# ATSAM4E16EA_AU_Main_Controller.net
KiCad netlist of a schematic drawn in Altium Designer
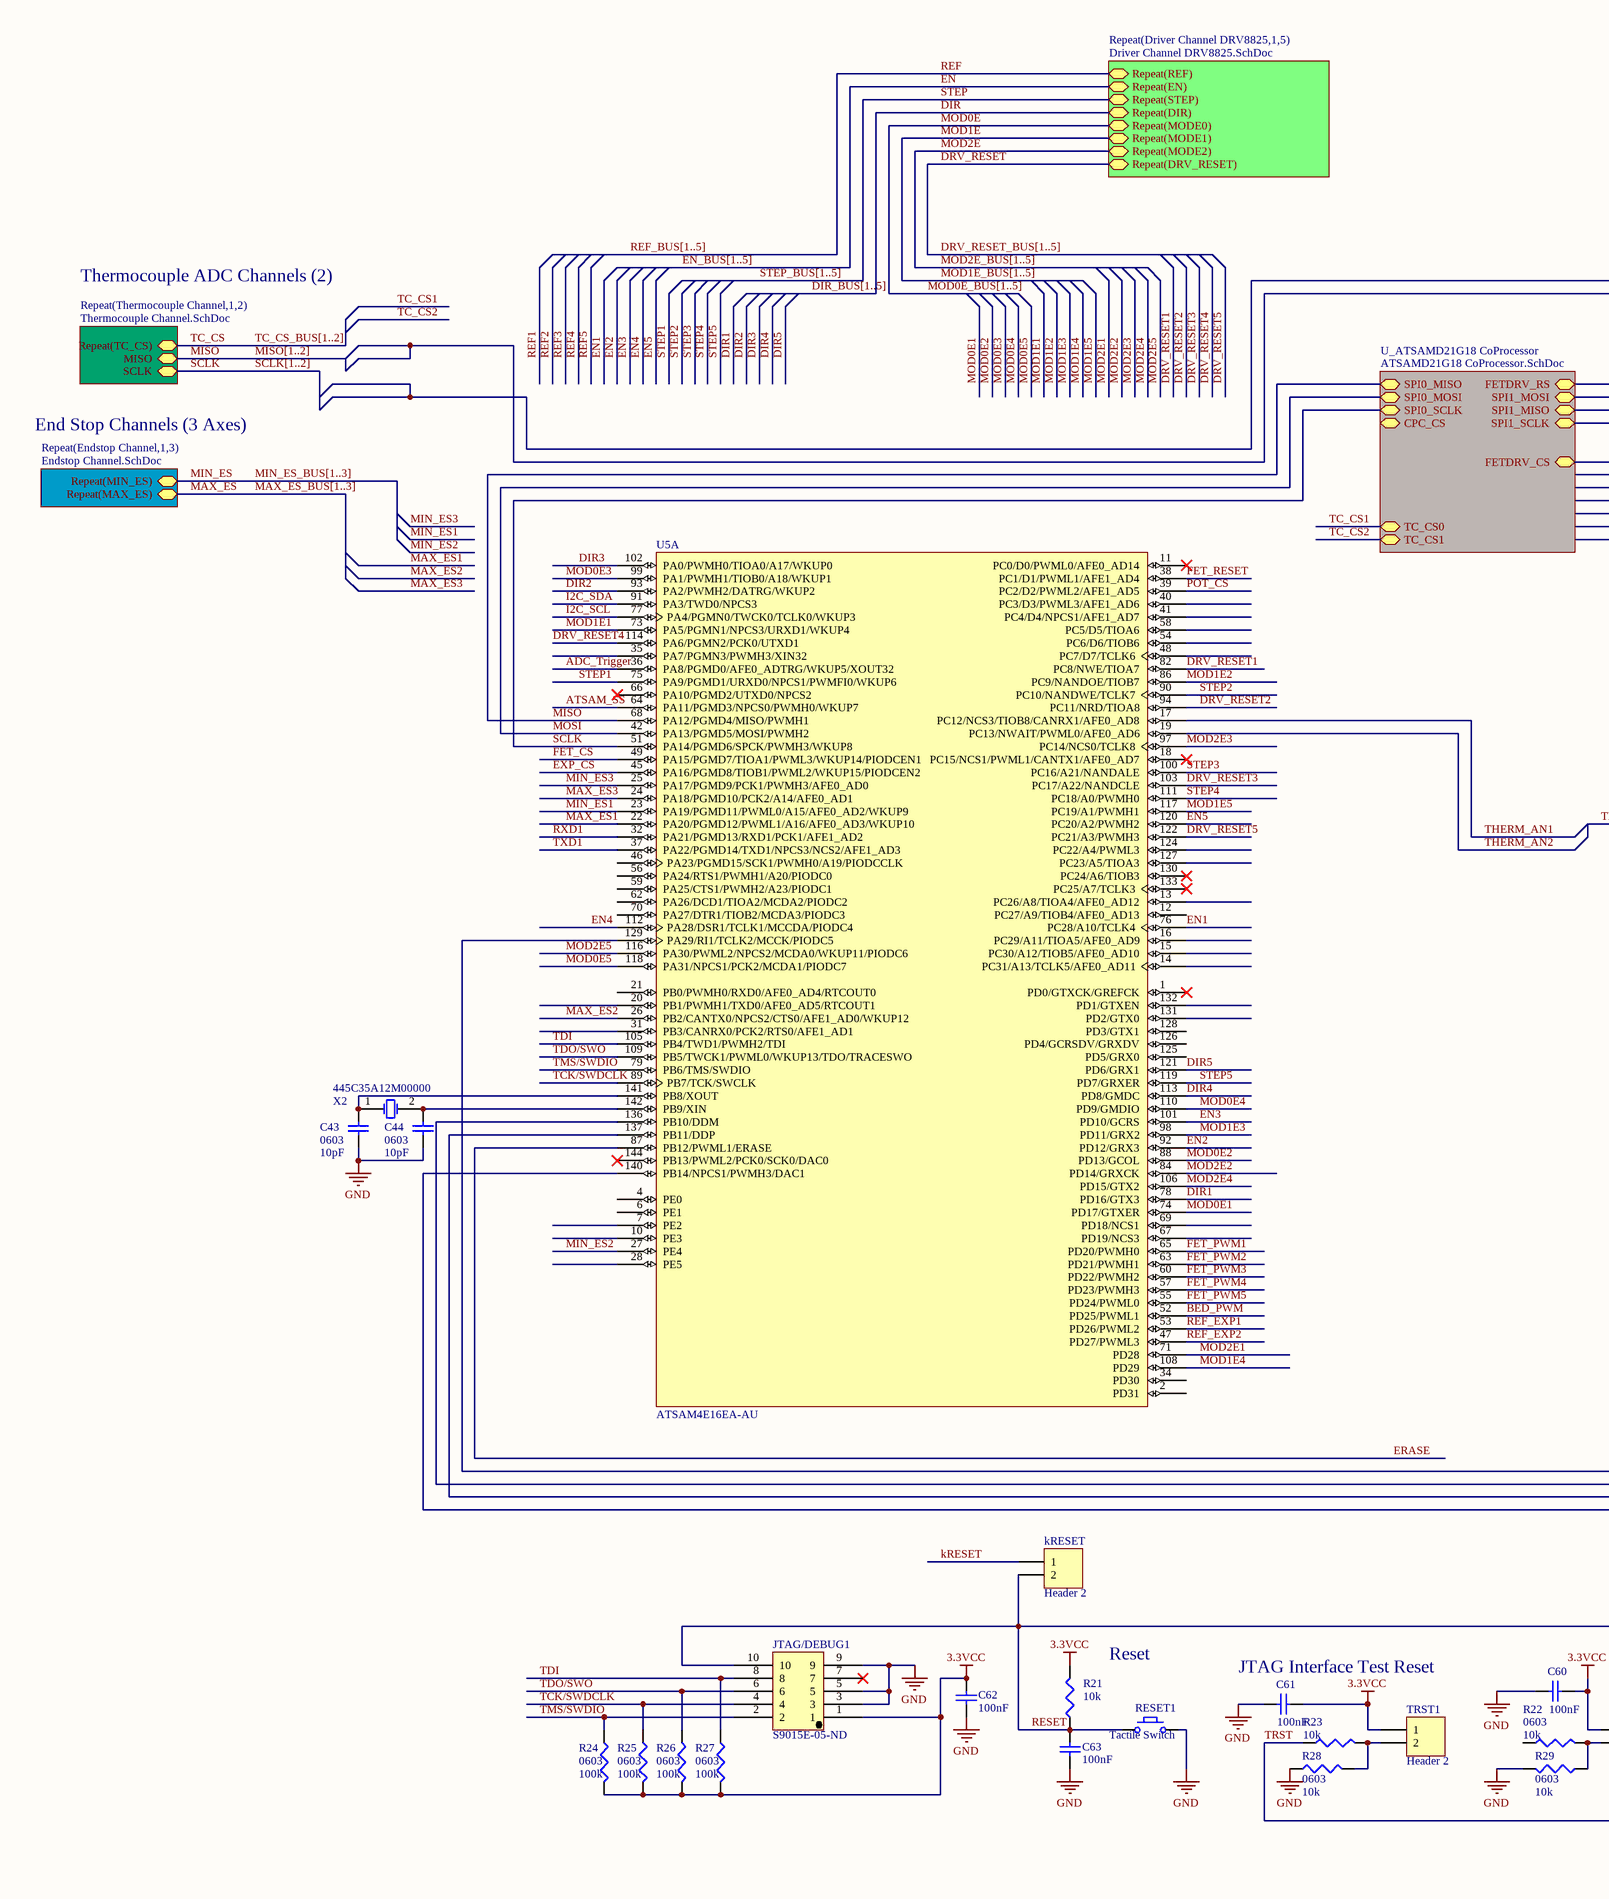
[diagram p0: ATSAM4E16EA_AU Main Controller.SchDoc, left]
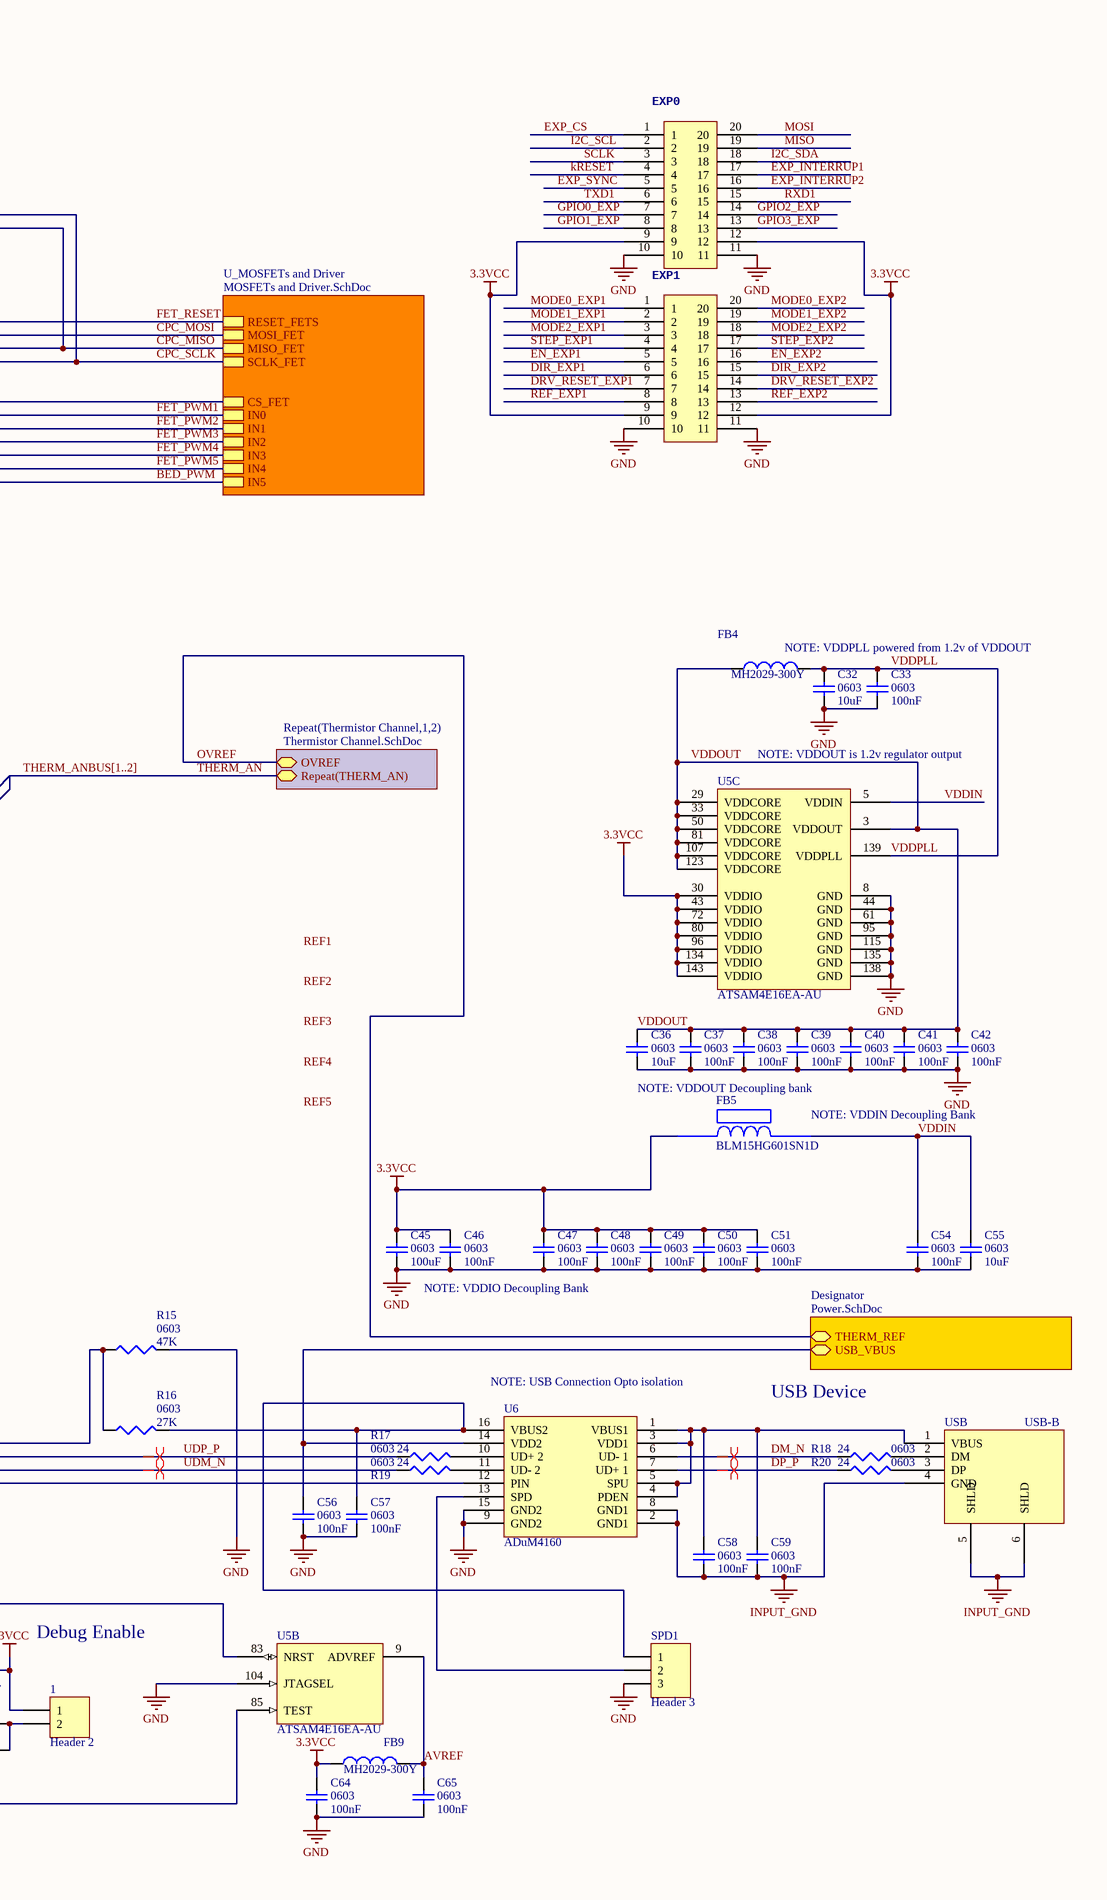
[diagram p1: ATSAM4E16EA_AU Main Controller.SchDoc, right]

(export (version "E")
  (design (tool "Eeschema 10.0.6"))
  (components
    (comp (ref "1")
      (value "Header 2")
      (footprint "HDR1X2")
      (description "Header, 2-Pin")
      (fields (field (name "PUBLISHER") "Altium Limited"))
      (libsource (lib "Miscellaneous Connectors") (part "Header 2"))
    )
    (comp (ref "C32")
      (value "0603")
      (footprint "1608[0603]")
      (description "Capacitor (Semiconductor SIM Model)")
      (fields (field (name "ALTIUM_VALUE") "10uF") (field (name "PUBLISHER") "Altium Limited"))
      (libsource (lib "Miscellaneous Devices") (part "Cap Semi"))
    )
    (comp (ref "C33")
      (value "0603")
      (footprint "1608[0603]")
      (description "Capacitor (Semiconductor SIM Model)")
      (fields (field (name "ALTIUM_VALUE") "100nF") (field (name "PUBLISHER") "Altium Limited"))
      (libsource (lib "Miscellaneous Devices") (part "Cap Semi"))
    )
    (comp (ref "C36")
      (value "0603")
      (footprint "1608[0603]")
      (description "Capacitor (Semiconductor SIM Model)")
      (fields (field (name "ALTIUM_VALUE") "10uF") (field (name "PUBLISHER") "Altium Limited"))
      (libsource (lib "Miscellaneous Devices") (part "Cap Semi"))
    )
    (comp (ref "C37")
      (value "0603")
      (footprint "1608[0603]")
      (description "Capacitor (Semiconductor SIM Model)")
      (fields (field (name "ALTIUM_VALUE") "100nF") (field (name "PUBLISHER") "Altium Limited"))
      (libsource (lib "Miscellaneous Devices") (part "Cap Semi"))
    )
    (comp (ref "C38")
      (value "0603")
      (footprint "1608[0603]")
      (description "Capacitor (Semiconductor SIM Model)")
      (fields (field (name "ALTIUM_VALUE") "100nF") (field (name "PUBLISHER") "Altium Limited"))
      (libsource (lib "Miscellaneous Devices") (part "Cap Semi"))
    )
    (comp (ref "C39")
      (value "0603")
      (footprint "1608[0603]")
      (description "Capacitor (Semiconductor SIM Model)")
      (fields (field (name "ALTIUM_VALUE") "100nF") (field (name "PUBLISHER") "Altium Limited"))
      (libsource (lib "Miscellaneous Devices") (part "Cap Semi"))
    )
    (comp (ref "C40")
      (value "0603")
      (footprint "1608[0603]")
      (description "Capacitor (Semiconductor SIM Model)")
      (fields (field (name "ALTIUM_VALUE") "100nF") (field (name "PUBLISHER") "Altium Limited"))
      (libsource (lib "Miscellaneous Devices") (part "Cap Semi"))
    )
    (comp (ref "C41")
      (value "0603")
      (footprint "1608[0603]")
      (description "Capacitor (Semiconductor SIM Model)")
      (fields (field (name "ALTIUM_VALUE") "100nF") (field (name "PUBLISHER") "Altium Limited"))
      (libsource (lib "Miscellaneous Devices") (part "Cap Semi"))
    )
    (comp (ref "C42")
      (value "0603")
      (footprint "1608[0603]")
      (description "Capacitor (Semiconductor SIM Model)")
      (fields (field (name "ALTIUM_VALUE") "100nF") (field (name "PUBLISHER") "Altium Limited"))
      (libsource (lib "Miscellaneous Devices") (part "Cap Semi"))
    )
    (comp (ref "C43")
      (value "0603")
      (footprint "1608[0603]")
      (description "Capacitor (Semiconductor SIM Model)")
      (fields (field (name "ALTIUM_VALUE") "10pF") (field (name "PUBLISHER") "Altium Limited"))
      (libsource (lib "Miscellaneous Devices") (part "Cap Semi"))
    )
    (comp (ref "C44")
      (value "0603")
      (footprint "1608[0603]")
      (description "Capacitor (Semiconductor SIM Model)")
      (fields (field (name "ALTIUM_VALUE") "10pF") (field (name "PUBLISHER") "Altium Limited"))
      (libsource (lib "Miscellaneous Devices") (part "Cap Semi"))
    )
    (comp (ref "C45")
      (value "0603")
      (footprint "1608[0603]")
      (description "Capacitor (Semiconductor SIM Model)")
      (fields (field (name "ALTIUM_VALUE") "100uF") (field (name "PUBLISHER") "Altium Limited"))
      (libsource (lib "Miscellaneous Devices") (part "Cap Semi"))
    )
    (comp (ref "C46")
      (value "0603")
      (footprint "1608[0603]")
      (description "Capacitor (Semiconductor SIM Model)")
      (fields (field (name "ALTIUM_VALUE") "100nF") (field (name "PUBLISHER") "Altium Limited"))
      (libsource (lib "Miscellaneous Devices") (part "Cap Semi"))
    )
    (comp (ref "C47")
      (value "0603")
      (footprint "1608[0603]")
      (description "Capacitor (Semiconductor SIM Model)")
      (fields (field (name "ALTIUM_VALUE") "100nF") (field (name "PUBLISHER") "Altium Limited"))
      (libsource (lib "Miscellaneous Devices") (part "Cap Semi"))
    )
    (comp (ref "C48")
      (value "0603")
      (footprint "1608[0603]")
      (description "Capacitor (Semiconductor SIM Model)")
      (fields (field (name "ALTIUM_VALUE") "100nF") (field (name "PUBLISHER") "Altium Limited"))
      (libsource (lib "Miscellaneous Devices") (part "Cap Semi"))
    )
    (comp (ref "C49")
      (value "0603")
      (footprint "1608[0603]")
      (description "Capacitor (Semiconductor SIM Model)")
      (fields (field (name "ALTIUM_VALUE") "100nF") (field (name "PUBLISHER") "Altium Limited"))
      (libsource (lib "Miscellaneous Devices") (part "Cap Semi"))
    )
    (comp (ref "C50")
      (value "0603")
      (footprint "1608[0603]")
      (description "Capacitor (Semiconductor SIM Model)")
      (fields (field (name "ALTIUM_VALUE") "100nF") (field (name "PUBLISHER") "Altium Limited"))
      (libsource (lib "Miscellaneous Devices") (part "Cap Semi"))
    )
    (comp (ref "C51")
      (value "0603")
      (footprint "1608[0603]")
      (description "Capacitor (Semiconductor SIM Model)")
      (fields (field (name "ALTIUM_VALUE") "100nF") (field (name "PUBLISHER") "Altium Limited"))
      (libsource (lib "Miscellaneous Devices") (part "Cap Semi"))
    )
    (comp (ref "C54")
      (value "0603")
      (footprint "1608[0603]")
      (description "Capacitor (Semiconductor SIM Model)")
      (fields (field (name "ALTIUM_VALUE") "100nF") (field (name "PUBLISHER") "Altium Limited"))
      (libsource (lib "Miscellaneous Devices") (part "Cap Semi"))
    )
    (comp (ref "C55")
      (value "0603")
      (footprint "1608[0603]")
      (description "Capacitor (Semiconductor SIM Model)")
      (fields (field (name "ALTIUM_VALUE") "10uF") (field (name "PUBLISHER") "Altium Limited"))
      (libsource (lib "Miscellaneous Devices") (part "Cap Semi"))
    )
    (comp (ref "C56")
      (value "0603")
      (footprint "1608[0603]")
      (description "Capacitor (Semiconductor SIM Model)")
      (fields (field (name "ALTIUM_VALUE") "100nF") (field (name "PUBLISHER") "Altium Limited"))
      (libsource (lib "Miscellaneous Devices") (part "Cap Semi"))
    )
    (comp (ref "C57")
      (value "0603")
      (footprint "1608[0603]")
      (description "Capacitor (Semiconductor SIM Model)")
      (fields (field (name "ALTIUM_VALUE") "100nF") (field (name "PUBLISHER") "Altium Limited"))
      (libsource (lib "Miscellaneous Devices") (part "Cap Semi"))
    )
    (comp (ref "C58")
      (value "0603")
      (footprint "1608[0603]")
      (description "Capacitor (Semiconductor SIM Model)")
      (fields (field (name "ALTIUM_VALUE") "100nF") (field (name "PUBLISHER") "Altium Limited"))
      (libsource (lib "Miscellaneous Devices") (part "Cap Semi"))
    )
    (comp (ref "C59")
      (value "0603")
      (footprint "1608[0603]")
      (description "Capacitor (Semiconductor SIM Model)")
      (fields (field (name "ALTIUM_VALUE") "100nF") (field (name "PUBLISHER") "Altium Limited"))
      (libsource (lib "Miscellaneous Devices") (part "Cap Semi"))
    )
    (comp (ref "C60")
      (value "100nF")
      (footprint "1608[0603]")
      (description "Capacitor (Semiconductor SIM Model)")
      (fields (field (name "Comment") "Cap Semi") (field (name "PUBLISHER") "Altium Limited"))
      (libsource (lib "Miscellaneous Devices") (part "Cap Semi"))
    )
    (comp (ref "C61")
      (value "100nF")
      (footprint "1608[0603]")
      (description "Capacitor (Semiconductor SIM Model)")
      (fields (field (name "Comment") "Cap Semi") (field (name "PUBLISHER") "Altium Limited"))
      (libsource (lib "Miscellaneous Devices") (part "Cap Semi"))
    )
    (comp (ref "C62")
      (value "100nF")
      (footprint "1608[0603]")
      (description "Capacitor (Semiconductor SIM Model)")
      (fields (field (name "Comment") "Cap Semi") (field (name "PUBLISHER") "Altium Limited"))
      (libsource (lib "Miscellaneous Devices") (part "Cap Semi"))
    )
    (comp (ref "C63")
      (value "100nF")
      (footprint "1608[0603]")
      (description "Capacitor (Semiconductor SIM Model)")
      (fields (field (name "Comment") "Cap Semi") (field (name "PUBLISHER") "Altium Limited"))
      (libsource (lib "Miscellaneous Devices") (part "Cap Semi"))
    )
    (comp (ref "C64")
      (value "0603")
      (footprint "1608[0603]")
      (description "Capacitor (Semiconductor SIM Model)")
      (fields (field (name "ALTIUM_VALUE") "100nF") (field (name "PUBLISHER") "Altium Limited"))
      (libsource (lib "Miscellaneous Devices") (part "Cap Semi"))
    )
    (comp (ref "C65")
      (value "0603")
      (footprint "1608[0603]")
      (description "Capacitor (Semiconductor SIM Model)")
      (fields (field (name "ALTIUM_VALUE") "100nF") (field (name "PUBLISHER") "Altium Limited"))
      (libsource (lib "Miscellaneous Devices") (part "Cap Semi"))
    )
    (comp (ref "EXP0")
      (value "10X2-0.1X0.05")
      (footprint "10X2-0.05X0.1")
      (fields (field (name "PUBLISHER") "UltiMachine"))
      (libsource (lib "ZMBo Schematic Library") (part "10X2-0.1X0.05"))
    )
    (comp (ref "EXP1")
      (value "10X2-0.1X0.05")
      (footprint "10X2-0.05X0.1")
      (fields (field (name "PUBLISHER") "UltiMachine"))
      (libsource (lib "ZMBo Schematic Library") (part "10X2-0.1X0.05"))
    )
    (comp (ref "FB4")
      (value "MH2029-300Y")
      (footprint "SM 0805 - gap trimmed")
      (description "Inductor")
      (fields (field (name "PUBLISHER") "Altium Limited"))
      (libsource (lib "Miscellaneous Devices") (part "Inductor"))
    )
    (comp (ref "FB5")
      (value "BLM15HG601SN1D")
      (footprint "BLM18PG121SN1D")
      (libsource (lib "AHD Part Library") (part "BLM15HG601SN1D"))
    )
    (comp (ref "FB9")
      (value "MH2029-300Y")
      (footprint "SM 0805 - gap trimmed")
      (description "Inductor")
      (fields (field (name "PUBLISHER") "Altium Limited"))
      (libsource (lib "Miscellaneous Devices") (part "Inductor"))
    )
    (comp (ref "JTAG/DEBUG1")
      (value "S9015E-05-ND")
      (footprint "S9015E-05-ND")
      (libsource (lib "AHD Part Library") (part "S9015E-05-ND"))
    )
    (comp (ref "kRESET")
      (value "Header 2")
      (footprint "HDR1X2")
      (description "Header, 2-Pin")
      (fields (field (name "PUBLISHER") "Altium Limited"))
      (libsource (lib "Miscellaneous Connectors") (part "Header 2"))
    )
    (comp (ref "R15")
      (value "0603")
      (footprint "J1-0603")
      (description "Resistor")
      (fields (field (name "ALTIUM_VALUE") "47K") (field (name "PUBLISHER") "Altium Limited"))
      (libsource (lib "Miscellaneous Devices") (part "Res3"))
    )
    (comp (ref "R16")
      (value "0603")
      (footprint "J1-0603")
      (description "Resistor")
      (fields (field (name "ALTIUM_VALUE") "27K") (field (name "PUBLISHER") "Altium Limited"))
      (libsource (lib "Miscellaneous Devices") (part "Res3"))
    )
    (comp (ref "R17")
      (value "0603")
      (footprint "J1-0603")
      (description "Resistor")
      (fields (field (name "ALTIUM_VALUE") "24") (field (name "PUBLISHER") "Altium Limited"))
      (libsource (lib "Miscellaneous Devices") (part "Res3"))
    )
    (comp (ref "R18")
      (value "0603")
      (footprint "J1-0603")
      (description "Resistor")
      (fields (field (name "ALTIUM_VALUE") "24") (field (name "PUBLISHER") "Altium Limited"))
      (libsource (lib "Miscellaneous Devices") (part "Res3"))
    )
    (comp (ref "R19")
      (value "0603")
      (footprint "J1-0603")
      (description "Resistor")
      (fields (field (name "ALTIUM_VALUE") "24") (field (name "PUBLISHER") "Altium Limited"))
      (libsource (lib "Miscellaneous Devices") (part "Res3"))
    )
    (comp (ref "R20")
      (value "0603")
      (footprint "J1-0603")
      (description "Resistor")
      (fields (field (name "ALTIUM_VALUE") "24") (field (name "PUBLISHER") "Altium Limited"))
      (libsource (lib "Miscellaneous Devices") (part "Res3"))
    )
    (comp (ref "R21")
      (value "10k")
      (footprint "J1-0603")
      (description "Resistor")
      (fields (field (name "Comment") "Res3") (field (name "PUBLISHER") "Altium Limited"))
      (libsource (lib "Miscellaneous Devices") (part "Res3"))
    )
    (comp (ref "R22")
      (value "0603")
      (footprint "J1-0603")
      (description "Resistor")
      (fields (field (name "ALTIUM_VALUE") "10k") (field (name "PUBLISHER") "Altium Limited"))
      (libsource (lib "Miscellaneous Devices") (part "Res3"))
    )
    (comp (ref "R23")
      (value "10k")
      (footprint "J1-0603")
      (description "Resistor")
      (fields (field (name "Comment") "Res3") (field (name "PUBLISHER") "Altium Limited"))
      (libsource (lib "Miscellaneous Devices") (part "Res3"))
    )
    (comp (ref "R24")
      (value "0603")
      (footprint "J1-0603")
      (description "Resistor")
      (fields (field (name "ALTIUM_VALUE") "100k") (field (name "PUBLISHER") "Altium Limited"))
      (libsource (lib "Miscellaneous Devices") (part "Res3"))
    )
    (comp (ref "R25")
      (value "0603")
      (footprint "J1-0603")
      (description "Resistor")
      (fields (field (name "ALTIUM_VALUE") "100k") (field (name "PUBLISHER") "Altium Limited"))
      (libsource (lib "Miscellaneous Devices") (part "Res3"))
    )
    (comp (ref "R26")
      (value "0603")
      (footprint "J1-0603")
      (description "Resistor")
      (fields (field (name "ALTIUM_VALUE") "100k") (field (name "PUBLISHER") "Altium Limited"))
      (libsource (lib "Miscellaneous Devices") (part "Res3"))
    )
    (comp (ref "R27")
      (value "0603")
      (footprint "J1-0603")
      (description "Resistor")
      (fields (field (name "ALTIUM_VALUE") "100k") (field (name "PUBLISHER") "Altium Limited"))
      (libsource (lib "Miscellaneous Devices") (part "Res3"))
    )
    (comp (ref "R28")
      (value "0603")
      (footprint "J1-0603")
      (description "Resistor")
      (fields (field (name "ALTIUM_VALUE") "10k") (field (name "PUBLISHER") "Altium Limited"))
      (libsource (lib "Miscellaneous Devices") (part "Res3"))
    )
    (comp (ref "R29")
      (value "0603")
      (footprint "J1-0603")
      (description "Resistor")
      (fields (field (name "ALTIUM_VALUE") "10k") (field (name "PUBLISHER") "Altium Limited"))
      (libsource (lib "Miscellaneous Devices") (part "Res3"))
    )
    (comp (ref "RESET1")
      (value "Tactile Switch")
      (footprint "TL3301")
      (libsource (lib "Adams Altium Library") (part "Tactile Switch"))
    )
    (comp (ref "SPD1")
      (value "Header 3")
      (footprint "HDR1X3")
      (description "Header, 3-Pin")
      (fields (field (name "PUBLISHER") "Altium Limited"))
      (libsource (lib "Miscellaneous Connectors") (part "Header 3"))
    )
    (comp (ref "TRST1")
      (value "Header 2")
      (footprint "HDR1X2")
      (description "Header, 2-Pin")
      (fields (field (name "PUBLISHER") "Altium Limited"))
      (libsource (lib "Miscellaneous Connectors") (part "Header 2"))
    )
    (comp (ref "U5")
      (value "ATSAM4E16EA-AU")
      (footprint "LQFP144_N")
      (libsource (lib "ZMBo Schematic Library") (part "ATML-ATSAM4EXEA-LQFP-144"))
    )
    (comp (ref "U6")
      (value "ADuM4160")
      (footprint "ADuM4160")
      (description "USB Opto Isolator")
      (libsource (lib "ZMBo Schematic Library") (part "ADuM4160"))
    )
    (comp (ref "USB")
      (value "USB-B")
      (footprint "PN61729")
      (libsource (lib "ZMBo Schematic Library") (part "USB-B"))
    )
    (comp (ref "X2")
      (value "445C35A12M00000")
      (footprint "445C35A12M00000")
      (description "Crystal Oscillator")
      (fields (field (name "PUBLISHER") "Altium Limited"))
      (libsource (lib "Miscellaneous Devices") (part "XTAL"))
    )
  )
  (nets
    (net (code "55") (name "/ADC_Trigger") (class "Default")
      (node (ref "U5") (pin "36") (pinfunction "PA8/PGMD0/AFE0_ADTRG/WKUP5/XOUT32_36") (pintype "bidirectional"))
    )
    (net (code "56") (name "/ATSAM_SS") (class "Default")
      (node (ref "U5") (pin "64") (pinfunction "PA11/PGMD3/NPCS0/PWMH0/WKUP7_64") (pintype "bidirectional"))
    )
    (net (code "57") (name "/AVREF") (class "Default")
      (node (ref "C65") (pin "2") (pinfunction "2_2") (pintype "passive"))
      (node (ref "FB9") (pin "2") (pinfunction "2_2") (pintype "passive"))
      (node (ref "U5") (pin "9") (pinfunction "ADVREF_9") (pintype "passive"))
    )
    (net (code "58") (name "/BED_PWM") (class "Default")
      (node (ref "U5") (pin "52") (pinfunction "PD25/PWML1_52") (pintype "bidirectional"))
    )
    (net (code "65") (name "/DIR1") (class "Default")
      (node (ref "U5") (pin "78") (pinfunction "PD16/GTX3_78") (pintype "bidirectional"))
    )
    (net (code "66") (name "/DIR2") (class "Default")
      (node (ref "U5") (pin "93") (pinfunction "PA2/PWMH2/DATRG/WKUP2_93") (pintype "bidirectional"))
    )
    (net (code "67") (name "/DIR3") (class "Default")
      (node (ref "U5") (pin "102") (pinfunction "PA0/PWMH0/TIOA0/A17/WKUP0_102") (pintype "bidirectional"))
    )
    (net (code "68") (name "/DIR4") (class "Default")
      (node (ref "U5") (pin "113") (pinfunction "PD8/GMDC_113") (pintype "bidirectional"))
    )
    (net (code "69") (name "/DIR5") (class "Default")
      (node (ref "U5") (pin "121") (pinfunction "PD6/GRX1_121") (pintype "bidirectional"))
    )
    (net (code "71") (name "/DIR_EXP1") (class "Default")
      (node (ref "EXP1") (pin "6") (pinfunction "6_6") (pintype "passive"))
    )
    (net (code "72") (name "/DIR_EXP2") (class "Default")
      (node (ref "EXP1") (pin "15") (pinfunction "15_15") (pintype "passive"))
    )
    (net (code "73") (name "/DM_N") (class "Default")
      (node (ref "R18") (pin "1") (pinfunction "1_1") (pintype "passive"))
      (node (ref "U6") (pin "6") (pinfunction "UD-_1_6") (pintype "passive"))
    )
    (net (code "74") (name "/DP_P") (class "Default")
      (node (ref "R20") (pin "1") (pinfunction "1_1") (pintype "passive"))
      (node (ref "U6") (pin "7") (pinfunction "UD+_1_7") (pintype "passive"))
    )
    (net (code "76") (name "/DRV_RESET1") (class "Default")
      (node (ref "U5") (pin "82") (pinfunction "PC8/NWE/TIOA7_82") (pintype "bidirectional"))
    )
    (net (code "77") (name "/DRV_RESET2") (class "Default")
      (node (ref "U5") (pin "94") (pinfunction "PC11/NRD/TIOA8_94") (pintype "bidirectional"))
    )
    (net (code "78") (name "/DRV_RESET3") (class "Default")
      (node (ref "U5") (pin "103") (pinfunction "PC17/A22/NANDCLE_103") (pintype "bidirectional"))
    )
    (net (code "79") (name "/DRV_RESET4") (class "Default")
      (node (ref "U5") (pin "114") (pinfunction "PA6/PGMN2/PCK0/UTXD1_114") (pintype "bidirectional"))
    )
    (net (code "80") (name "/DRV_RESET5") (class "Default")
      (node (ref "U5") (pin "122") (pinfunction "PC21/A3/PWMH3_122") (pintype "bidirectional"))
    )
    (net (code "82") (name "/DRV_RESET_EXP1") (class "Default")
      (node (ref "EXP1") (pin "7") (pinfunction "7_7") (pintype "passive"))
    )
    (net (code "83") (name "/DRV_RESET_EXP2") (class "Default")
      (node (ref "EXP1") (pin "14") (pinfunction "14_14") (pintype "passive"))
    )
    (net (code "85") (name "/EN1") (class "Default")
      (node (ref "U5") (pin "76") (pinfunction "PC28/A10/TCLK4_76") (pintype "bidirectional"))
    )
    (net (code "86") (name "/EN2") (class "Default")
      (node (ref "U5") (pin "92") (pinfunction "PD12/GRX3_92") (pintype "bidirectional"))
    )
    (net (code "87") (name "/EN3") (class "Default")
      (node (ref "U5") (pin "101") (pinfunction "PD10/GCRS_101") (pintype "bidirectional"))
    )
    (net (code "88") (name "/EN4") (class "Default")
      (node (ref "U5") (pin "112") (pinfunction "PA28/DSR1/TCLK1/MCCDA/PIODC4_112") (pintype "bidirectional"))
    )
    (net (code "89") (name "/EN5") (class "Default")
      (node (ref "U5") (pin "120") (pinfunction "PC20/A2/PWMH2_120") (pintype "bidirectional"))
    )
    (net (code "91") (name "/EN_EXP1") (class "Default")
      (node (ref "EXP1") (pin "5") (pinfunction "5_5") (pintype "passive"))
    )
    (net (code "92") (name "/EN_EXP2") (class "Default")
      (node (ref "EXP1") (pin "16") (pinfunction "16_16") (pintype "passive"))
    )
    (net (code "93") (name "/ERASE") (class "Default")
      (node (ref "U5") (pin "87") (pinfunction "PB12/PWML1/ERASE_87") (pintype "bidirectional"))
    )
    (net (code "94") (name "/EXP_CS") (class "Default")
      (node (ref "EXP0") (pin "1") (pinfunction "1_1") (pintype "passive"))
      (node (ref "U5") (pin "45") (pinfunction "PA16/PGMD8/TIOB1/PWML2/WKUP15/PIODCEN2_45") (pintype "bidirectional"))
    )
    (net (code "95") (name "/EXP_INTERRUP1") (class "Default")
      (node (ref "EXP0") (pin "17") (pinfunction "17_17") (pintype "passive"))
    )
    (net (code "96") (name "/EXP_INTERRUP2") (class "Default")
      (node (ref "EXP0") (pin "16") (pinfunction "16_16") (pintype "passive"))
    )
    (net (code "97") (name "/EXP_SYNC") (class "Default")
      (node (ref "EXP0") (pin "5") (pinfunction "5_5") (pintype "passive"))
    )
    (net (code "98") (name "/FET_CS") (class "Default")
      (node (ref "U5") (pin "49") (pinfunction "PA15/PGMD7/TIOA1/PWML3/WKUP14/PIODCEN1_49") (pintype "bidirectional"))
    )
    (net (code "99") (name "/FET_PWM1") (class "Default")
      (node (ref "U5") (pin "65") (pinfunction "PD20/PWMH0_65") (pintype "bidirectional"))
    )
    (net (code "100") (name "/FET_PWM2") (class "Default")
      (node (ref "U5") (pin "63") (pinfunction "PD21/PWMH1_63") (pintype "bidirectional"))
    )
    (net (code "101") (name "/FET_PWM3") (class "Default")
      (node (ref "U5") (pin "60") (pinfunction "PD22/PWMH2_60") (pintype "bidirectional"))
    )
    (net (code "102") (name "/FET_PWM4") (class "Default")
      (node (ref "U5") (pin "57") (pinfunction "PD23/PWMH3_57") (pintype "bidirectional"))
    )
    (net (code "103") (name "/FET_PWM5") (class "Default")
      (node (ref "U5") (pin "55") (pinfunction "PD24/PWML0_55") (pintype "bidirectional"))
    )
    (net (code "104") (name "/FET_RESET") (class "Default")
      (node (ref "U5") (pin "38") (pinfunction "PC1/D1/PWML1/AFE1_AD4_38") (pintype "bidirectional"))
    )
    (net (code "105") (name "/GPIO0_EXP") (class "Default")
      (node (ref "EXP0") (pin "7") (pinfunction "7_7") (pintype "passive"))
    )
    (net (code "106") (name "/GPIO1_EXP") (class "Default")
      (node (ref "EXP0") (pin "8") (pinfunction "8_8") (pintype "passive"))
    )
    (net (code "107") (name "/GPIO2_EXP") (class "Default")
      (node (ref "EXP0") (pin "14") (pinfunction "14_14") (pintype "passive"))
    )
    (net (code "108") (name "/GPIO3_EXP") (class "Default")
      (node (ref "EXP0") (pin "13") (pinfunction "13_13") (pintype "passive"))
    )
    (net (code "109") (name "/I2C_SCL") (class "Default")
      (node (ref "EXP0") (pin "2") (pinfunction "2_2") (pintype "passive"))
      (node (ref "U5") (pin "77") (pinfunction "PA4/PGMN0/TWCK0/TCLK0/WKUP3_77") (pintype "bidirectional"))
    )
    (net (code "110") (name "/I2C_SDA") (class "Default")
      (node (ref "EXP0") (pin "18") (pinfunction "18_18") (pintype "passive"))
      (node (ref "U5") (pin "91") (pinfunction "PA3/TWD0/NPCS3_91") (pintype "bidirectional"))
    )
    (net (code "112") (name "/MAX_ES1") (class "Default")
      (node (ref "U5") (pin "22") (pinfunction "PA20/PGMD12/PWML1/A16/AFE0_AD3/WKUP10_22") (pintype "bidirectional"))
    )
    (net (code "113") (name "/MAX_ES2") (class "Default")
      (node (ref "U5") (pin "26") (pinfunction "PB2/CANTX0/NPCS2/CTS0/AFE1_AD0/WKUP12_26") (pintype "bidirectional"))
    )
    (net (code "114") (name "/MAX_ES3") (class "Default")
      (node (ref "U5") (pin "24") (pinfunction "PA18/PGMD10/PCK2/A14/AFE0_AD1_24") (pintype "bidirectional"))
    )
    (net (code "117") (name "/MIN_ES1") (class "Default")
      (node (ref "U5") (pin "23") (pinfunction "PA19/PGMD11/PWML0/A15/AFE0_AD2/WKUP9_23") (pintype "bidirectional"))
    )
    (net (code "118") (name "/MIN_ES2") (class "Default")
      (node (ref "U5") (pin "27") (pinfunction "PE4_27") (pintype "bidirectional"))
    )
    (net (code "119") (name "/MIN_ES3") (class "Default")
      (node (ref "U5") (pin "25") (pinfunction "PA17/PGMD9/PCK1/PWMH3/AFE0_AD0_25") (pintype "bidirectional"))
    )
    (net (code "121") (name "/MISO") (class "Default")
      (node (ref "EXP0") (pin "19") (pinfunction "19_19") (pintype "passive"))
      (node (ref "U5") (pin "68") (pinfunction "PA12/PGMD4/MISO/PWMH1_68") (pintype "bidirectional"))
    )
    (net (code "124") (name "/MOD0E1") (class "Default")
      (node (ref "U5") (pin "74") (pinfunction "PD17/GTXER_74") (pintype "bidirectional"))
    )
    (net (code "125") (name "/MOD0E2") (class "Default")
      (node (ref "U5") (pin "88") (pinfunction "PD13/GCOL_88") (pintype "bidirectional"))
    )
    (net (code "126") (name "/MOD0E3") (class "Default")
      (node (ref "U5") (pin "99") (pinfunction "PA1/PWMH1/TIOB0/A18/WKUP1_99") (pintype "bidirectional"))
    )
    (net (code "127") (name "/MOD0E4") (class "Default")
      (node (ref "U5") (pin "110") (pinfunction "PD9/GMDIO_110") (pintype "bidirectional"))
    )
    (net (code "128") (name "/MOD0E5") (class "Default")
      (node (ref "U5") (pin "118") (pinfunction "PA31/NPCS1/PCK2/MCDA1/PIODC7_118") (pintype "bidirectional"))
    )
    (net (code "131") (name "/MOD1E1") (class "Default")
      (node (ref "U5") (pin "73") (pinfunction "PA5/PGMN1/NPCS3/URXD1/WKUP4_73") (pintype "bidirectional"))
    )
    (net (code "132") (name "/MOD1E2") (class "Default")
      (node (ref "U5") (pin "86") (pinfunction "PC9/NANDOE/TIOB7_86") (pintype "bidirectional"))
    )
    (net (code "133") (name "/MOD1E3") (class "Default")
      (node (ref "U5") (pin "98") (pinfunction "PD11/GRX2_98") (pintype "bidirectional"))
    )
    (net (code "134") (name "/MOD1E4") (class "Default")
      (node (ref "U5") (pin "108") (pinfunction "PD29_108") (pintype "bidirectional"))
    )
    (net (code "135") (name "/MOD1E5") (class "Default")
      (node (ref "U5") (pin "117") (pinfunction "PC19/A1/PWMH1_117") (pintype "bidirectional"))
    )
    (net (code "138") (name "/MOD2E1") (class "Default")
      (node (ref "U5") (pin "71") (pinfunction "PD28_71") (pintype "bidirectional"))
    )
    (net (code "139") (name "/MOD2E2") (class "Default")
      (node (ref "U5") (pin "84") (pinfunction "PD14/GRXCK_84") (pintype "bidirectional"))
    )
    (net (code "140") (name "/MOD2E3") (class "Default")
      (node (ref "U5") (pin "97") (pinfunction "PC14/NCS0/TCLK8_97") (pintype "bidirectional"))
    )
    (net (code "141") (name "/MOD2E4") (class "Default")
      (node (ref "U5") (pin "106") (pinfunction "PD15/GTX2_106") (pintype "bidirectional"))
    )
    (net (code "142") (name "/MOD2E5") (class "Default")
      (node (ref "U5") (pin "116") (pinfunction "PA30/PWML2/NPCS2/MCDA0/WKUP11/PIODC6_116") (pintype "bidirectional"))
    )
    (net (code "144") (name "/MODE0_EXP1") (class "Default")
      (node (ref "EXP1") (pin "1") (pinfunction "1_1") (pintype "passive"))
    )
    (net (code "145") (name "/MODE0_EXP2") (class "Default")
      (node (ref "EXP1") (pin "20") (pinfunction "20_20") (pintype "passive"))
    )
    (net (code "146") (name "/MODE1_EXP1") (class "Default")
      (node (ref "EXP1") (pin "2") (pinfunction "2_2") (pintype "passive"))
    )
    (net (code "147") (name "/MODE1_EXP2") (class "Default")
      (node (ref "EXP1") (pin "19") (pinfunction "19_19") (pintype "passive"))
    )
    (net (code "148") (name "/MODE2_EXP1") (class "Default")
      (node (ref "EXP1") (pin "3") (pinfunction "3_3") (pintype "passive"))
    )
    (net (code "149") (name "/MODE2_EXP2") (class "Default")
      (node (ref "EXP1") (pin "18") (pinfunction "18_18") (pintype "passive"))
    )
    (net (code "150") (name "/MOSI") (class "Default")
      (node (ref "EXP0") (pin "20") (pinfunction "20_20") (pintype "passive"))
      (node (ref "U5") (pin "42") (pinfunction "PA13/PGMD5/MOSI/PWMH2_42") (pintype "bidirectional"))
    )
    (net (code "152") (name "/POT_CS") (class "Default")
      (node (ref "U5") (pin "39") (pinfunction "PC2/D2/PWML2/AFE1_AD5_39") (pintype "bidirectional"))
    )
    (net (code "160") (name "/REF_EXP1") (class "Default")
      (node (ref "EXP1") (pin "8") (pinfunction "8_8") (pintype "passive"))
      (node (ref "U5") (pin "53") (pinfunction "PD26/PWML2_53") (pintype "bidirectional"))
    )
    (net (code "161") (name "/REF_EXP2") (class "Default")
      (node (ref "EXP1") (pin "13") (pinfunction "13_13") (pintype "passive"))
      (node (ref "U5") (pin "47") (pinfunction "PD27/PWML3_47") (pintype "bidirectional"))
    )
    (net (code "162") (name "/RESET") (class "Default")
      (node (ref "C63") (pin "2") (pinfunction "2_2") (pintype "passive"))
      (node (ref "JTAG/DEBUG1") (pin "10") (pinfunction "10_10") (pintype "passive"))
      (node (ref "R21") (pin "1") (pinfunction "1_1") (pintype "passive"))
      (node (ref "RESET1") (pin "1") (pintype "passive"))
      (node (ref "U5") (pin "83") (pinfunction "NRST_83") (pintype "bidirectional"))
      (node (ref "kRESET") (pin "2") (pinfunction "2_2") (pintype "passive"))
    )
    (net (code "163") (name "/RXD1") (class "Default")
      (node (ref "EXP0") (pin "15") (pinfunction "15_15") (pintype "passive"))
      (node (ref "U5") (pin "32") (pinfunction "PA21/PGMD13/RXD1/PCK1/AFE1_AD2_32") (pintype "bidirectional"))
    )
    (net (code "164") (name "/SCLK") (class "Default")
      (node (ref "EXP0") (pin "3") (pinfunction "3_3") (pintype "passive"))
      (node (ref "U5") (pin "51") (pinfunction "PA14/PGMD6/SPCK/PWMH3/WKUP8_51") (pintype "bidirectional"))
    )
    (net (code "167") (name "/STEP1") (class "Default")
      (node (ref "U5") (pin "75") (pinfunction "PA9/PGMD1/URXD0/NPCS1/PWMFI0/WKUP6_75") (pintype "bidirectional"))
    )
    (net (code "168") (name "/STEP2") (class "Default")
      (node (ref "U5") (pin "90") (pinfunction "PC10/NANDWE/TCLK7_90") (pintype "bidirectional"))
    )
    (net (code "169") (name "/STEP3") (class "Default")
      (node (ref "U5") (pin "100") (pinfunction "PC16/A21/NANDALE_100") (pintype "bidirectional"))
    )
    (net (code "170") (name "/STEP4") (class "Default")
      (node (ref "U5") (pin "111") (pinfunction "PC18/A0/PWMH0_111") (pintype "bidirectional"))
    )
    (net (code "171") (name "/STEP5") (class "Default")
      (node (ref "U5") (pin "119") (pinfunction "PD7/GRXER_119") (pintype "bidirectional"))
    )
    (net (code "173") (name "/STEP_EXP1") (class "Default")
      (node (ref "EXP1") (pin "4") (pinfunction "4_4") (pintype "passive"))
    )
    (net (code "174") (name "/STEP_EXP2") (class "Default")
      (node (ref "EXP1") (pin "17") (pinfunction "17_17") (pintype "passive"))
    )
    (net (code "175") (name "/TCK{slash}SWDCLK") (class "Default")
      (node (ref "JTAG/DEBUG1") (pin "4") (pinfunction "4_4") (pintype "passive"))
      (node (ref "R25") (pin "1") (pinfunction "1_1") (pintype "passive"))
      (node (ref "U5") (pin "89") (pinfunction "PB7/TCK/SWCLK_89") (pintype "bidirectional"))
    )
    (net (code "180") (name "/TDI") (class "Default")
      (node (ref "JTAG/DEBUG1") (pin "8") (pinfunction "8_8") (pintype "passive"))
      (node (ref "R27") (pin "1") (pinfunction "1_1") (pintype "passive"))
      (node (ref "U5") (pin "105") (pinfunction "PB4/TWD1/PWMH2/TDI_105") (pintype "bidirectional"))
    )
    (net (code "181") (name "/TDO{slash}SWO") (class "Default")
      (node (ref "JTAG/DEBUG1") (pin "6") (pinfunction "6_6") (pintype "passive"))
      (node (ref "R26") (pin "1") (pinfunction "1_1") (pintype "passive"))
      (node (ref "U5") (pin "109") (pinfunction "PB5/TWCK1/PWML0/WKUP13/TDO/TRACESWO_109") (pintype "bidirectional"))
    )
    (net (code "183") (name "/THERM_AN1") (class "Default")
      (node (ref "U5") (pin "17") (pinfunction "PC12/NCS3/TIOB8/CANRX1/AFE0_AD8_17") (pintype "bidirectional"))
    )
    (net (code "184") (name "/THERM_AN2") (class "Default")
      (node (ref "U5") (pin "19") (pinfunction "PC13/NWAIT/PWML0/AFE0_AD6_19") (pintype "bidirectional"))
    )
    (net (code "186") (name "/TMS{slash}SWDIO") (class "Default")
      (node (ref "JTAG/DEBUG1") (pin "2") (pinfunction "2_2") (pintype "passive"))
      (node (ref "R24") (pin "1") (pinfunction "1_1") (pintype "passive"))
      (node (ref "U5") (pin "79") (pinfunction "PB6/TMS/SWDIO_79") (pintype "bidirectional"))
    )
    (net (code "187") (name "/TRST") (class "Default")
      (node (ref "R23") (pin "1") (pinfunction "1_1") (pintype "passive"))
      (node (ref "U5") (pin "85") (pinfunction "TEST_85") (pintype "input"))
    )
    (net (code "188") (name "/TXD1") (class "Default")
      (node (ref "EXP0") (pin "6") (pinfunction "6_6") (pintype "passive"))
      (node (ref "U5") (pin "37") (pinfunction "PA22/PGMD14/TXD1/NPCS3/NCS2/AFE1_AD3_37") (pintype "bidirectional"))
    )
    (net (code "189") (name "/UDM_N") (class "Default")
      (node (ref "R19") (pin "1") (pinfunction "1_1") (pintype "passive"))
      (node (ref "U5") (pin "137") (pinfunction "PB11/DDP_137") (pintype "bidirectional"))
    )
    (net (code "190") (name "/UDP_P") (class "Default")
      (node (ref "R17") (pin "1") (pinfunction "1_1") (pintype "passive"))
      (node (ref "U5") (pin "136") (pinfunction "PB10/DDM_136") (pintype "bidirectional"))
    )
    (net (code "191") (name "/USB_VBUS") (class "Default")
      (node (ref "C56") (pin "2") (pinfunction "2_2") (pintype "passive"))
      (node (ref "U6") (pin "14") (pinfunction "VDD2_14") (pintype "passive"))
    )
    (net (code "192") (name "/VDDIN") (class "Default")
      (node (ref "C54") (pin "2") (pinfunction "2_2") (pintype "passive"))
      (node (ref "C55") (pin "2") (pinfunction "2_2") (pintype "passive"))
      (node (ref "FB5") (pin "2") (pinfunction "2_2") (pintype "passive"))
      (node (ref "U5") (pin "5") (pinfunction "VDDIN_5") (pintype "power_in"))
    )
    (net (code "193") (name "/VDDOUT") (class "Default")
      (node (ref "C36") (pin "2") (pinfunction "2_2") (pintype "passive"))
      (node (ref "C37") (pin "2") (pinfunction "2_2") (pintype "passive"))
      (node (ref "C38") (pin "2") (pinfunction "2_2") (pintype "passive"))
      (node (ref "C39") (pin "2") (pinfunction "2_2") (pintype "passive"))
      (node (ref "C40") (pin "2") (pinfunction "2_2") (pintype "passive"))
      (node (ref "C41") (pin "2") (pinfunction "2_2") (pintype "passive"))
      (node (ref "C42") (pin "2") (pinfunction "2_2") (pintype "passive"))
      (node (ref "FB4") (pin "1") (pinfunction "1_1") (pintype "passive"))
      (node (ref "U5") (pin "107") (pinfunction "VDDCORE_107") (pintype "power_in"))
      (node (ref "U5") (pin "123") (pinfunction "VDDCORE_123") (pintype "power_in"))
      (node (ref "U5") (pin "29") (pinfunction "VDDCORE_29") (pintype "power_in"))
      (node (ref "U5") (pin "3") (pinfunction "VDDOUT_3") (pintype "power_in"))
      (node (ref "U5") (pin "33") (pinfunction "VDDCORE_33") (pintype "power_in"))
      (node (ref "U5") (pin "50") (pinfunction "VDDCORE_50") (pintype "power_in"))
      (node (ref "U5") (pin "81") (pinfunction "VDDCORE_81") (pintype "power_in"))
    )
    (net (code "194") (name "/VDDPLL") (class "Default")
      (node (ref "C32") (pin "2") (pinfunction "2_2") (pintype "passive"))
      (node (ref "C33") (pin "2") (pinfunction "2_2") (pintype "passive"))
      (node (ref "FB4") (pin "2") (pinfunction "2_2") (pintype "passive"))
      (node (ref "U5") (pin "139") (pinfunction "VDDPLL_139") (pintype "power_in"))
    )
    (net (code "195") (name "/kRESET") (class "Default")
      (node (ref "EXP0") (pin "4") (pinfunction "4_4") (pintype "passive"))
      (node (ref "kRESET") (pin "1") (pinfunction "1_1") (pintype "passive"))
    )
    (net (code "196") (name "3.3VCC") (class "Default")
      (node (ref "1") (pin "1") (pinfunction "1_1") (pintype "passive"))
      (node (ref "C45") (pin "2") (pinfunction "2_2") (pintype "passive"))
      (node (ref "C46") (pin "2") (pinfunction "2_2") (pintype "passive"))
      (node (ref "C47") (pin "2") (pinfunction "2_2") (pintype "passive"))
      (node (ref "C48") (pin "2") (pinfunction "2_2") (pintype "passive"))
      (node (ref "C49") (pin "2") (pinfunction "2_2") (pintype "passive"))
      (node (ref "C50") (pin "2") (pinfunction "2_2") (pintype "passive"))
      (node (ref "C51") (pin "2") (pinfunction "2_2") (pintype "passive"))
      (node (ref "C60") (pin "2") (pinfunction "2_2") (pintype "passive"))
      (node (ref "C61") (pin "2") (pinfunction "2_2") (pintype "passive"))
      (node (ref "C62") (pin "2") (pinfunction "2_2") (pintype "passive"))
      (node (ref "C64") (pin "2") (pinfunction "2_2") (pintype "passive"))
      (node (ref "EXP0") (pin "12") (pinfunction "12_12") (pintype "passive"))
      (node (ref "EXP0") (pin "9") (pinfunction "9_9") (pintype "passive"))
      (node (ref "EXP1") (pin "12") (pinfunction "12_12") (pintype "passive"))
      (node (ref "EXP1") (pin "9") (pinfunction "9_9") (pintype "passive"))
      (node (ref "FB5") (pin "1") (pinfunction "1_1") (pintype "passive"))
      (node (ref "FB9") (pin "1") (pinfunction "1_1") (pintype "passive"))
      (node (ref "JTAG/DEBUG1") (pin "1") (pinfunction "1_1") (pintype "passive"))
      (node (ref "R21") (pin "2") (pinfunction "2_2") (pintype "passive"))
      (node (ref "R24") (pin "2") (pinfunction "2_2") (pintype "passive"))
      (node (ref "R25") (pin "2") (pinfunction "2_2") (pintype "passive"))
      (node (ref "R26") (pin "2") (pinfunction "2_2") (pintype "passive"))
      (node (ref "R27") (pin "2") (pinfunction "2_2") (pintype "passive"))
      (node (ref "TRST1") (pin "1") (pinfunction "1_1") (pintype "passive"))
      (node (ref "U5") (pin "134") (pinfunction "VDDIO_134") (pintype "power_in"))
      (node (ref "U5") (pin "143") (pinfunction "VDDIO_143") (pintype "power_in"))
      (node (ref "U5") (pin "30") (pinfunction "VDDIO_30") (pintype "power_in"))
      (node (ref "U5") (pin "43") (pinfunction "VDDIO_43") (pintype "power_in"))
      (node (ref "U5") (pin "72") (pinfunction "VDDIO_72") (pintype "power_in"))
      (node (ref "U5") (pin "80") (pinfunction "VDDIO_80") (pintype "power_in"))
      (node (ref "U5") (pin "96") (pinfunction "VDDIO_96") (pintype "power_in"))
    )
    (net (code "197") (name "GND") (class "Default")
      (node (ref "C32") (pin "1") (pinfunction "1_1") (pintype "passive"))
      (node (ref "C33") (pin "1") (pinfunction "1_1") (pintype "passive"))
      (node (ref "C36") (pin "1") (pinfunction "1_1") (pintype "passive"))
      (node (ref "C37") (pin "1") (pinfunction "1_1") (pintype "passive"))
      (node (ref "C38") (pin "1") (pinfunction "1_1") (pintype "passive"))
      (node (ref "C39") (pin "1") (pinfunction "1_1") (pintype "passive"))
      (node (ref "C40") (pin "1") (pinfunction "1_1") (pintype "passive"))
      (node (ref "C41") (pin "1") (pinfunction "1_1") (pintype "passive"))
      (node (ref "C42") (pin "1") (pinfunction "1_1") (pintype "passive"))
      (node (ref "C43") (pin "1") (pinfunction "1_1") (pintype "passive"))
      (node (ref "C44") (pin "1") (pinfunction "1_1") (pintype "passive"))
      (node (ref "C45") (pin "1") (pinfunction "1_1") (pintype "passive"))
      (node (ref "C46") (pin "1") (pinfunction "1_1") (pintype "passive"))
      (node (ref "C47") (pin "1") (pinfunction "1_1") (pintype "passive"))
      (node (ref "C48") (pin "1") (pinfunction "1_1") (pintype "passive"))
      (node (ref "C49") (pin "1") (pinfunction "1_1") (pintype "passive"))
      (node (ref "C50") (pin "1") (pinfunction "1_1") (pintype "passive"))
      (node (ref "C51") (pin "1") (pinfunction "1_1") (pintype "passive"))
      (node (ref "C54") (pin "1") (pinfunction "1_1") (pintype "passive"))
      (node (ref "C55") (pin "1") (pinfunction "1_1") (pintype "passive"))
      (node (ref "C56") (pin "1") (pinfunction "1_1") (pintype "passive"))
      (node (ref "C57") (pin "1") (pinfunction "1_1") (pintype "passive"))
      (node (ref "C60") (pin "1") (pinfunction "1_1") (pintype "passive"))
      (node (ref "C61") (pin "1") (pinfunction "1_1") (pintype "passive"))
      (node (ref "C62") (pin "1") (pinfunction "1_1") (pintype "passive"))
      (node (ref "C63") (pin "1") (pinfunction "1_1") (pintype "passive"))
      (node (ref "C64") (pin "1") (pinfunction "1_1") (pintype "passive"))
      (node (ref "C65") (pin "1") (pinfunction "1_1") (pintype "passive"))
      (node (ref "EXP0") (pin "10") (pinfunction "10_10") (pintype "passive"))
      (node (ref "EXP0") (pin "11") (pinfunction "11_11") (pintype "passive"))
      (node (ref "EXP1") (pin "10") (pinfunction "10_10") (pintype "passive"))
      (node (ref "EXP1") (pin "11") (pinfunction "11_11") (pintype "passive"))
      (node (ref "JTAG/DEBUG1") (pin "3") (pinfunction "3_3") (pintype "passive"))
      (node (ref "JTAG/DEBUG1") (pin "5") (pinfunction "5_5") (pintype "passive"))
      (node (ref "JTAG/DEBUG1") (pin "9") (pinfunction "9_9") (pintype "passive"))
      (node (ref "R15") (pin "2") (pinfunction "2_2") (pintype "passive"))
      (node (ref "R28") (pin "1") (pinfunction "1_1") (pintype "passive"))
      (node (ref "R29") (pin "2") (pinfunction "2_2") (pintype "passive"))
      (node (ref "RESET1") (pin "2") (pintype "passive"))
      (node (ref "SPD1") (pin "3") (pinfunction "3_3") (pintype "passive"))
      (node (ref "U5") (pin "104") (pinfunction "JTAGSEL_104") (pintype "input"))
      (node (ref "U5") (pin "115") (pinfunction "GND_115") (pintype "power_in"))
      (node (ref "U5") (pin "135") (pinfunction "GND_135") (pintype "power_in"))
      (node (ref "U5") (pin "138") (pinfunction "GND_138") (pintype "power_in"))
      (node (ref "U5") (pin "44") (pinfunction "GND_44") (pintype "power_in"))
      (node (ref "U5") (pin "61") (pinfunction "GND_61") (pintype "power_in"))
      (node (ref "U5") (pin "8") (pinfunction "GND_8") (pintype "power_in"))
      (node (ref "U5") (pin "95") (pinfunction "GND_95") (pintype "power_in"))
      (node (ref "U6") (pin "15") (pinfunction "GND2_15") (pintype "passive"))
      (node (ref "U6") (pin "9") (pinfunction "GND2_9") (pintype "passive"))
    )
    (net (code "198") (name "INPUT_GND") (class "Default")
      (node (ref "C58") (pin "1") (pinfunction "1_1") (pintype "passive"))
      (node (ref "C59") (pin "1") (pinfunction "1_1") (pintype "passive"))
      (node (ref "U6") (pin "2") (pinfunction "GND1_2") (pintype "passive"))
      (node (ref "U6") (pin "8") (pinfunction "GND1_8") (pintype "passive"))
      (node (ref "USB") (pin "4") (pinfunction "GND_4") (pintype "passive"))
      (node (ref "USB") (pin "5") (pinfunction "SHLD_5") (pintype "passive"))
      (node (ref "USB") (pin "6") (pinfunction "SHLD_6") (pintype "passive"))
    )
    (net (code "199") (name "Net-(1-Pad2)") (class "Default")
      (node (ref "1") (pin "2") (pinfunction "2_2") (pintype "passive"))
      (node (ref "R22") (pin "2") (pinfunction "2_2") (pintype "passive"))
      (node (ref "R29") (pin "1") (pinfunction "1_1") (pintype "passive"))
    )
    (net (code "200") (name "Net-(R23-Pad2)") (class "Default")
      (node (ref "R23") (pin "2") (pinfunction "2_2") (pintype "passive"))
      (node (ref "R28") (pin "2") (pinfunction "2_2") (pintype "passive"))
      (node (ref "TRST1") (pin "2") (pinfunction "2_2") (pintype "passive"))
    )
    (net (code "201") (name "Net-(U5A-PA29{slash}RI1{slash}TCLK2{slash}MCCK{slash}PIODC5)") (class "Default")
      (node (ref "R15") (pin "1") (pinfunction "1_1") (pintype "passive"))
      (node (ref "R16") (pin "1") (pinfunction "1_1") (pintype "passive"))
      (node (ref "U5") (pin "129") (pinfunction "PA29/RI1/TCLK2/MCCK/PIODC5_129") (pintype "bidirectional"))
    )
    (net (code "202") (name "Net-(U5A-PB8{slash}XOUT)") (class "Default")
      (node (ref "C43") (pin "2") (pinfunction "2_2") (pintype "passive"))
      (node (ref "U5") (pin "141") (pinfunction "PB8/XOUT_141") (pintype "bidirectional"))
      (node (ref "X2") (pin "1") (pinfunction "OSC1_1") (pintype "passive"))
    )
    (net (code "203") (name "Net-(U5A-PB9{slash}XIN)") (class "Default")
      (node (ref "C44") (pin "2") (pinfunction "2_2") (pintype "passive"))
      (node (ref "U5") (pin "142") (pinfunction "PB9/XIN_142") (pintype "bidirectional"))
      (node (ref "X2") (pin "2") (pinfunction "OSC2_2") (pintype "passive"))
    )
    (net (code "204") (name "Net-(U5A-PB14{slash}NPCS1{slash}PWMH3{slash}DAC1)") (class "Default")
      (node (ref "U5") (pin "140") (pinfunction "PB14/NPCS1/PWMH3/DAC1_140") (pintype "bidirectional"))
      (node (ref "U6") (pin "12") (pinfunction "PIN_12") (pintype "passive"))
    )
    (net (code "205") (name "Net-(U6-PDEN)") (class "Default")
      (node (ref "C58") (pin "2") (pinfunction "2_2") (pintype "passive"))
      (node (ref "C59") (pin "2") (pinfunction "2_2") (pintype "passive"))
      (node (ref "U6") (pin "1") (pinfunction "VBUS1_1") (pintype "passive"))
      (node (ref "U6") (pin "3") (pinfunction "VDD1_3") (pintype "passive"))
      (node (ref "U6") (pin "4") (pinfunction "PDEN_4") (pintype "passive"))
      (node (ref "U6") (pin "5") (pinfunction "SPU_5") (pintype "passive"))
      (node (ref "USB") (pin "1") (pinfunction "VBUS_1") (pintype "passive"))
    )
    (net (code "206") (name "Net-(U6-SPD)") (class "Default")
      (node (ref "SPD1") (pin "2") (pinfunction "2_2") (pintype "passive"))
      (node (ref "U6") (pin "13") (pinfunction "SPD_13") (pintype "passive"))
    )
    (net (code "207") (name "Net-(U6-UD+_2)") (class "Default")
      (node (ref "R17") (pin "2") (pinfunction "2_2") (pintype "passive"))
      (node (ref "U6") (pin "10") (pinfunction "UD+_2_10") (pintype "passive"))
    )
    (net (code "208") (name "Net-(U6-UD-_2)") (class "Default")
      (node (ref "R19") (pin "2") (pinfunction "2_2") (pintype "passive"))
      (node (ref "U6") (pin "11") (pinfunction "UD-_2_11") (pintype "passive"))
    )
    (net (code "209") (name "Net-(U6-VBUS2)") (class "Default")
      (node (ref "C57") (pin "2") (pinfunction "2_2") (pintype "passive"))
      (node (ref "R16") (pin "2") (pinfunction "2_2") (pintype "passive"))
      (node (ref "SPD1") (pin "1") (pinfunction "1_1") (pintype "passive"))
      (node (ref "U6") (pin "16") (pinfunction "VBUS2_16") (pintype "passive"))
    )
    (net (code "210") (name "Net-(USB-DM)") (class "Default")
      (node (ref "R18") (pin "2") (pinfunction "2_2") (pintype "passive"))
      (node (ref "USB") (pin "2") (pinfunction "DM_2") (pintype "passive"))
    )
    (net (code "211") (name "Net-(USB-DP)") (class "Default")
      (node (ref "R20") (pin "2") (pinfunction "2_2") (pintype "passive"))
      (node (ref "USB") (pin "3") (pinfunction "DP_3") (pintype "passive"))
    )
    (net (code "212") (name "unconnected-(JTAG/DEBUG1-Pad7)") (class "Default")
      (node (ref "JTAG/DEBUG1") (pin "7") (pinfunction "7_7") (pintype "passive+no_connect"))
    )
    (net (code "213") (name "unconnected-(R22-Pad1)") (class "Default")
      (node (ref "R22") (pin "1") (pinfunction "1_1") (pintype "passive"))
    )
    (net (code "214") (name "unconnected-(U5A-PA7{slash}PGMN3{slash}PWMH3{slash}XIN32-Pad35)") (class "Default")
      (node (ref "U5") (pin "35") (pinfunction "PA7/PGMN3/PWMH3/XIN32_35") (pintype "bidirectional"))
    )
    (net (code "215") (name "unconnected-(U5A-PA10{slash}PGMD2{slash}UTXD0{slash}NPCS2-Pad66)") (class "Default")
      (node (ref "U5") (pin "66") (pinfunction "PA10/PGMD2/UTXD0/NPCS2_66") (pintype "bidirectional+no_connect"))
    )
    (net (code "216") (name "unconnected-(U5A-PA23{slash}PGMD15{slash}SCK1{slash}PWMH0{slash}A19{slash}PIODCCLK-Pad46)") (class "Default")
      (node (ref "U5") (pin "46") (pinfunction "PA23/PGMD15/SCK1/PWMH0/A19/PIODCCLK_46") (pintype "bidirectional"))
    )
    (net (code "217") (name "unconnected-(U5A-PA24{slash}RTS1{slash}PWMH1{slash}A20{slash}PIODC0-Pad56)") (class "Default")
      (node (ref "U5") (pin "56") (pinfunction "PA24/RTS1/PWMH1/A20/PIODC0_56") (pintype "bidirectional"))
    )
    (net (code "218") (name "unconnected-(U5A-PA25{slash}CTS1{slash}PWMH2{slash}A23{slash}PIODC1-Pad59)") (class "Default")
      (node (ref "U5") (pin "59") (pinfunction "PA25/CTS1/PWMH2/A23/PIODC1_59") (pintype "bidirectional"))
    )
    (net (code "219") (name "unconnected-(U5A-PA26{slash}DCD1{slash}TIOA2{slash}MCDA2{slash}PIODC2-Pad62)") (class "Default")
      (node (ref "U5") (pin "62") (pinfunction "PA26/DCD1/TIOA2/MCDA2/PIODC2_62") (pintype "bidirectional"))
    )
    (net (code "220") (name "unconnected-(U5A-PA27{slash}DTR1{slash}TIOB2{slash}MCDA3{slash}PIODC3-Pad70)") (class "Default")
      (node (ref "U5") (pin "70") (pinfunction "PA27/DTR1/TIOB2/MCDA3/PIODC3_70") (pintype "bidirectional"))
    )
    (net (code "221") (name "unconnected-(U5A-PB0{slash}PWMH0{slash}RXD0{slash}AFE0_AD4{slash}RTCOUT0-Pad21)") (class "Default")
      (node (ref "U5") (pin "21") (pinfunction "PB0/PWMH0/RXD0/AFE0_AD4/RTCOUT0_21") (pintype "bidirectional"))
    )
    (net (code "222") (name "unconnected-(U5A-PB1{slash}PWMH1{slash}TXD0{slash}AFE0_AD5{slash}RTCOUT1-Pad20)") (class "Default")
      (node (ref "U5") (pin "20") (pinfunction "PB1/PWMH1/TXD0/AFE0_AD5/RTCOUT1_20") (pintype "bidirectional"))
    )
    (net (code "223") (name "unconnected-(U5A-PB3{slash}CANRX0{slash}PCK2{slash}RTS0{slash}AFE1_AD1-Pad31)") (class "Default")
      (node (ref "U5") (pin "31") (pinfunction "PB3/CANRX0/PCK2/RTS0/AFE1_AD1_31") (pintype "bidirectional"))
    )
    (net (code "224") (name "unconnected-(U5A-PB13{slash}PWML2{slash}PCK0{slash}SCK0{slash}DAC0-Pad144)") (class "Default")
      (node (ref "U5") (pin "144") (pinfunction "PB13/PWML2/PCK0/SCK0/DAC0_144") (pintype "bidirectional+no_connect"))
    )
    (net (code "225") (name "unconnected-(U5A-PC0{slash}D0{slash}PWML0{slash}AFE0_AD14-Pad11)") (class "Default")
      (node (ref "U5") (pin "11") (pinfunction "PC0/D0/PWML0/AFE0_AD14_11") (pintype "bidirectional+no_connect"))
    )
    (net (code "226") (name "unconnected-(U5A-PC3{slash}D3{slash}PWML3{slash}AFE1_AD6-Pad40)") (class "Default")
      (node (ref "U5") (pin "40") (pinfunction "PC3/D3/PWML3/AFE1_AD6_40") (pintype "bidirectional"))
    )
    (net (code "227") (name "unconnected-(U5A-PC4{slash}D4{slash}NPCS1{slash}AFE1_AD7-Pad41)") (class "Default")
      (node (ref "U5") (pin "41") (pinfunction "PC4/D4/NPCS1/AFE1_AD7_41") (pintype "bidirectional"))
    )
    (net (code "228") (name "unconnected-(U5A-PC5{slash}D5{slash}TIOA6-Pad58)") (class "Default")
      (node (ref "U5") (pin "58") (pinfunction "PC5/D5/TIOA6_58") (pintype "bidirectional"))
    )
    (net (code "229") (name "unconnected-(U5A-PC6{slash}D6{slash}TIOB6-Pad54)") (class "Default")
      (node (ref "U5") (pin "54") (pinfunction "PC6/D6/TIOB6_54") (pintype "bidirectional"))
    )
    (net (code "230") (name "unconnected-(U5A-PC7{slash}D7{slash}TCLK6-Pad48)") (class "Default")
      (node (ref "U5") (pin "48") (pinfunction "PC7/D7/TCLK6_48") (pintype "bidirectional"))
    )
    (net (code "231") (name "unconnected-(U5A-PC15{slash}NCS1{slash}PWML1{slash}CANTX1{slash}AFE0_AD7-Pad18)") (class "Default")
      (node (ref "U5") (pin "18") (pinfunction "PC15/NCS1/PWML1/CANTX1/AFE0_AD7_18") (pintype "bidirectional+no_connect"))
    )
    (net (code "232") (name "unconnected-(U5A-PC22{slash}A4{slash}PWML3-Pad124)") (class "Default")
      (node (ref "U5") (pin "124") (pinfunction "PC22/A4/PWML3_124") (pintype "bidirectional"))
    )
    (net (code "233") (name "unconnected-(U5A-PC23{slash}A5{slash}TIOA3-Pad127)") (class "Default")
      (node (ref "U5") (pin "127") (pinfunction "PC23/A5/TIOA3_127") (pintype "bidirectional"))
    )
    (net (code "234") (name "unconnected-(U5A-PC24{slash}A6{slash}TIOB3-Pad130)") (class "Default")
      (node (ref "U5") (pin "130") (pinfunction "PC24/A6/TIOB3_130") (pintype "bidirectional+no_connect"))
    )
    (net (code "235") (name "unconnected-(U5A-PC25{slash}A7{slash}TCLK3-Pad133)") (class "Default")
      (node (ref "U5") (pin "133") (pinfunction "PC25/A7/TCLK3_133") (pintype "bidirectional+no_connect"))
    )
    (net (code "236") (name "unconnected-(U5A-PC26{slash}A8{slash}TIOA4{slash}AFE0_AD12-Pad13)") (class "Default")
      (node (ref "U5") (pin "13") (pinfunction "PC26/A8/TIOA4/AFE0_AD12_13") (pintype "bidirectional"))
    )
    (net (code "237") (name "unconnected-(U5A-PC27{slash}A9{slash}TIOB4{slash}AFE0_AD13-Pad12)") (class "Default")
      (node (ref "U5") (pin "12") (pinfunction "PC27/A9/TIOB4/AFE0_AD13_12") (pintype "bidirectional"))
    )
    (net (code "238") (name "unconnected-(U5A-PC29{slash}A11{slash}TIOA5{slash}AFE0_AD9-Pad16)") (class "Default")
      (node (ref "U5") (pin "16") (pinfunction "PC29/A11/TIOA5/AFE0_AD9_16") (pintype "bidirectional"))
    )
    (net (code "239") (name "unconnected-(U5A-PC30{slash}A12{slash}TIOB5{slash}AFE0_AD10-Pad15)") (class "Default")
      (node (ref "U5") (pin "15") (pinfunction "PC30/A12/TIOB5/AFE0_AD10_15") (pintype "bidirectional"))
    )
    (net (code "240") (name "unconnected-(U5A-PC31{slash}A13{slash}TCLK5{slash}AFE0_AD11-Pad14)") (class "Default")
      (node (ref "U5") (pin "14") (pinfunction "PC31/A13/TCLK5/AFE0_AD11_14") (pintype "bidirectional"))
    )
    (net (code "241") (name "unconnected-(U5A-PD0{slash}GTXCK{slash}GREFCK-Pad1)") (class "Default")
      (node (ref "U5") (pin "1") (pinfunction "PD0/GTXCK/GREFCK_1") (pintype "bidirectional+no_connect"))
    )
    (net (code "242") (name "unconnected-(U5A-PD1{slash}GTXEN-Pad132)") (class "Default")
      (node (ref "U5") (pin "132") (pinfunction "PD1/GTXEN_132") (pintype "bidirectional"))
    )
    (net (code "243") (name "unconnected-(U5A-PD2{slash}GTX0-Pad131)") (class "Default")
      (node (ref "U5") (pin "131") (pinfunction "PD2/GTX0_131") (pintype "bidirectional"))
    )
    (net (code "244") (name "unconnected-(U5A-PD3{slash}GTX1-Pad128)") (class "Default")
      (node (ref "U5") (pin "128") (pinfunction "PD3/GTX1_128") (pintype "bidirectional"))
    )
    (net (code "245") (name "unconnected-(U5A-PD4{slash}GCRSDV{slash}GRXDV-Pad126)") (class "Default")
      (node (ref "U5") (pin "126") (pinfunction "PD4/GCRSDV/GRXDV_126") (pintype "bidirectional"))
    )
    (net (code "246") (name "unconnected-(U5A-PD5{slash}GRX0-Pad125)") (class "Default")
      (node (ref "U5") (pin "125") (pinfunction "PD5/GRX0_125") (pintype "bidirectional"))
    )
    (net (code "247") (name "unconnected-(U5A-PD18{slash}NCS1-Pad69)") (class "Default")
      (node (ref "U5") (pin "69") (pinfunction "PD18/NCS1_69") (pintype "bidirectional"))
    )
    (net (code "248") (name "unconnected-(U5A-PD19{slash}NCS3-Pad67)") (class "Default")
      (node (ref "U5") (pin "67") (pinfunction "PD19/NCS3_67") (pintype "bidirectional"))
    )
    (net (code "249") (name "unconnected-(U5A-PD30-Pad34)") (class "Default")
      (node (ref "U5") (pin "34") (pinfunction "PD30_34") (pintype "bidirectional"))
    )
    (net (code "250") (name "unconnected-(U5A-PD31-Pad2)") (class "Default")
      (node (ref "U5") (pin "2") (pinfunction "PD31_2") (pintype "bidirectional"))
    )
    (net (code "251") (name "unconnected-(U5A-PE0-Pad4)") (class "Default")
      (node (ref "U5") (pin "4") (pinfunction "PE0_4") (pintype "bidirectional"))
    )
    (net (code "252") (name "unconnected-(U5A-PE1-Pad6)") (class "Default")
      (node (ref "U5") (pin "6") (pinfunction "PE1_6") (pintype "bidirectional"))
    )
    (net (code "253") (name "unconnected-(U5A-PE2-Pad7)") (class "Default")
      (node (ref "U5") (pin "7") (pinfunction "PE2_7") (pintype "bidirectional"))
    )
    (net (code "254") (name "unconnected-(U5A-PE3-Pad10)") (class "Default")
      (node (ref "U5") (pin "10") (pinfunction "PE3_10") (pintype "bidirectional"))
    )
    (net (code "255") (name "unconnected-(U5A-PE5-Pad28)") (class "Default")
      (node (ref "U5") (pin "28") (pinfunction "PE5_28") (pintype "bidirectional"))
    )
  )
)
